# TDA2030.net
KiCad netlist of a schematic drawn in Altium Designer
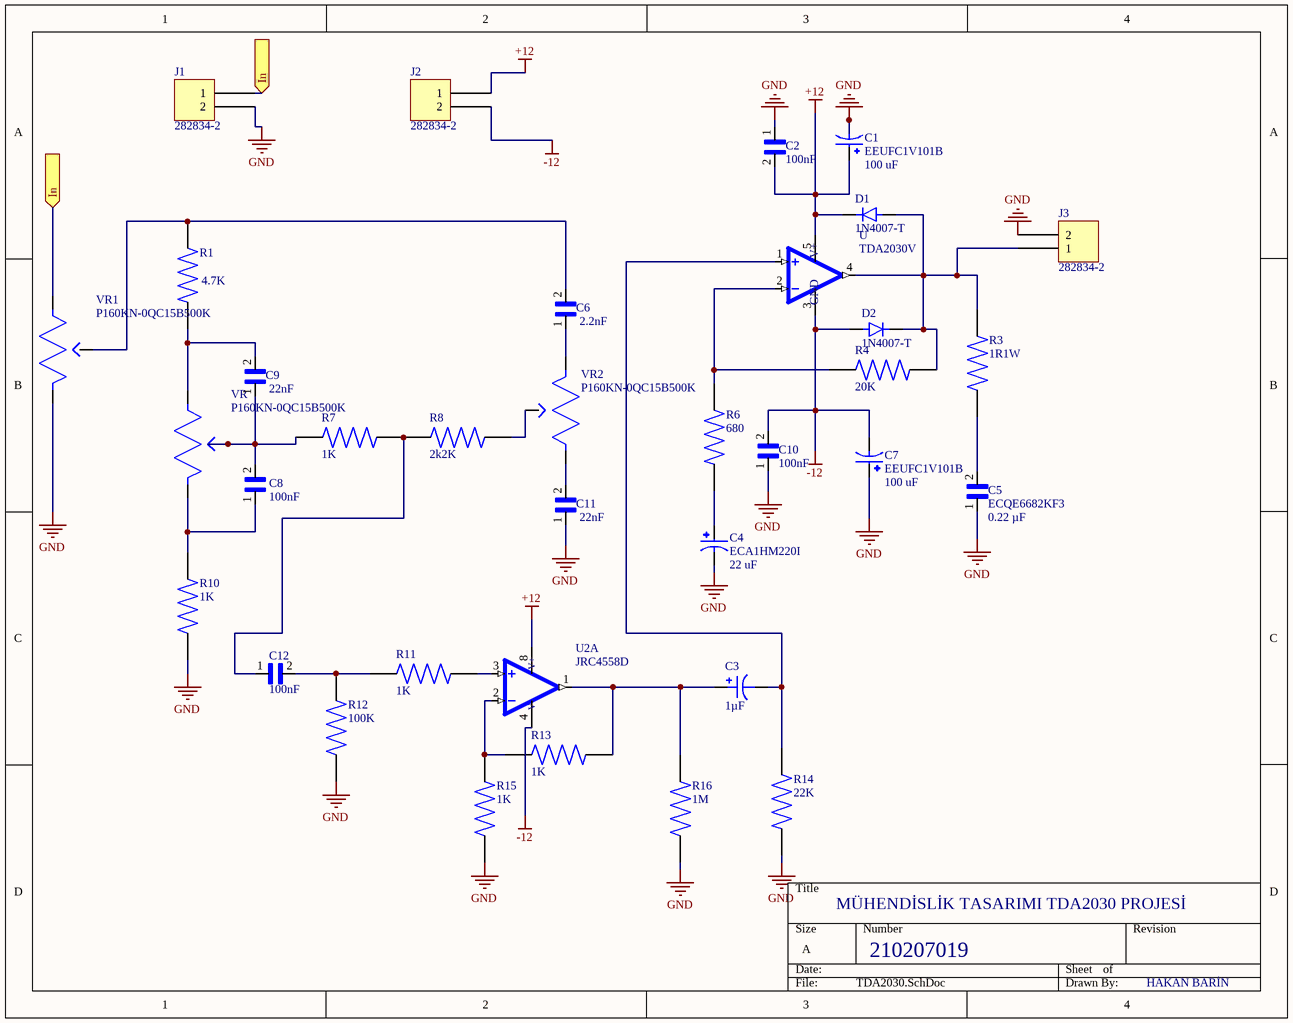
[diagram p0: TDA2030.SchDoc]

(export (version "E")
  (design (tool "Eeschema 10.0.6"))
  (components
    (comp (ref "C1")
      (value "EEUFC1V101B")
      (footprint "CAPPRD500W60D800H1150")
      (description "100F 35V Aluminum Electrolytic Capacitors Radial, Can 2000 Hrs @ 105C")
      (fields (field (name "MF") "Panasonic") (field (name "ALTIUM_VALUE") "100 uF"))
      (libsource (lib "EEUFC1V101B") (part "EEUFC1V101B"))
    )
    (comp (ref "C2")
      (value "100nF")
      (footprint "CAPRB500W50L450T300H550")
      (description "Cap Ceramic 1uF 50V X7R 10% Radial 5mm 125Â°C Tape")
      (fields (field (name "MF") "TDK") (field (name "MP") "FG24X7R1H105KRT06"))
      (libsource (lib "") (part "FG24X7R1H105KRT06_2"))
    )
    (comp (ref "C3")
      (value "1µF")
      (footprint "CAP TH ALUM ELEC D5.00mm S2.00mm H11.00mm")
      (description "CAP ALUM 1UF 20% 50V RADIAL")
      (fields (field (name "PART NUMBER") "RFS-50V010ME3#5") (field (name "MANUFACTURER") "Elna America"))
      (libsource (lib "Celestial Altium Library - altium_library") (part "Polarised Capacitor"))
    )
    (comp (ref "C4")
      (value "ECA1HM220I")
      (footprint "CAPPRD250W50D500H1100")
      (fields
        (field (name "ALTIUM_VALUE") "22 uF")
        (field (name "MF") "Panasonic")
        (field (name "MP") "ECA-1HM220I")
      )
      (libsource (lib "ECA1HM220I") (part "ECA1HM220I"))
    )
    (comp (ref "C5")
      (value "ECQE6682KF3")
      (footprint "CAPRR500W60L1200T490H1500")
      (fields (field (name "ALTIUM_VALUE") "0.22 µF"))
      (libsource (lib "ECQE6682KF3") (part "ECQE6682KF3"))
    )
    (comp (ref "C6")
      (value "2.2nF")
      (footprint "CAPRB500W50L450T300H550")
      (description "Cap Ceramic 1uF 50V X7R 10% Radial 5mm 125Â°C Tape")
      (fields (field (name "MF") "TDK") (field (name "MP") "FG24X7R1H105KRT06"))
      (libsource (lib "FG24X7R1H105KRT06") (part "FG24X7R1H105KRT06"))
    )
    (comp (ref "C7")
      (value "EEUFC1V101B")
      (footprint "CAPPRD500W60D800H1150")
      (description "100F 35V Aluminum Electrolytic Capacitors Radial, Can 2000 Hrs @ 105C")
      (fields (field (name "MF") "Panasonic") (field (name "ALTIUM_VALUE") "100 uF"))
      (libsource (lib "EEUFC1V101B") (part "EEUFC1V101B"))
    )
    (comp (ref "C8")
      (value "100nF")
      (footprint "CAPRB500W50L450T300H550")
      (description "Cap Ceramic 1uF 50V X7R 10% Radial 5mm 125Â°C Tape")
      (fields (field (name "MF") "TDK") (field (name "MP") "FG24X7R1H105KRT06"))
      (libsource (lib "FG24X7R1H105KRT06") (part "FG24X7R1H105KRT06"))
    )
    (comp (ref "C9")
      (value "22nF")
      (footprint "CAPRB500W50L450T300H550")
      (description "Cap Ceramic 1uF 50V X7R 10% Radial 5mm 125Â°C Tape")
      (fields (field (name "MF") "TDK") (field (name "MP") "FG24X7R1H105KRT06"))
      (libsource (lib "FG24X7R1H105KRT06") (part "FG24X7R1H105KRT06"))
    )
    (comp (ref "C10")
      (value "100nF")
      (footprint "CAPRB500W50L450T300H550")
      (description "Cap Ceramic 1uF 50V X7R 10% Radial 5mm 125Â°C Tape")
      (fields (field (name "MF") "TDK") (field (name "MP") "FG24X7R1H105KRT06"))
      (libsource (lib "FG24X7R1H105KRT06") (part "FG24X7R1H105KRT06"))
    )
    (comp (ref "C11")
      (value "22nF")
      (footprint "CAPRB500W50L450T300H550")
      (description "Cap Ceramic 1uF 50V X7R 10% Radial 5mm 125Â°C Tape")
      (fields (field (name "MF") "TDK") (field (name "MP") "FG24X7R1H105KRT06"))
      (libsource (lib "FG24X7R1H105KRT06") (part "FG24X7R1H105KRT06"))
    )
    (comp (ref "C12")
      (value "100nF")
      (footprint "CAPRB500W50L450T300H550")
      (description "Cap Ceramic 1uF 50V X7R 10% Radial 5mm 125Â°C Tape")
      (fields (field (name "MF") "TDK") (field (name "MP") "FG24X7R1H105KRT06"))
      (libsource (lib "") (part "FG24X7R1H105KRT06_1"))
    )
    (comp (ref "D1")
      (value "1N4007-T")
      (footprint "DIOAD780W78L463D236")
      (description "Diode Standard 1A 1000V 1Vf DO41 ¦ Diodes Inc 1N4007-T")
      (fields (field (name "MF") "Diodes Incorporated"))
      (libsource (lib "1N4007-T") (part "1N4007-T"))
    )
    (comp (ref "D2")
      (value "1N4007-T")
      (footprint "DIOAD780W78L463D236")
      (description "Diode Standard 1A 1000V 1Vf DO41 ¦ Diodes Inc 1N4007-T")
      (fields (field (name "MF") "Diodes Incorporated"))
      (libsource (lib "1N4007-T") (part "1N4007-T"))
    )
    (comp (ref "J1")
      (value "282834-2")
      (footprint "TE 282834-2")
      (description "TERM BLK 2P SIDE ENT 2.54MM PCB")
      (fields (field (name "MANUFACTURER") "TE Connectivity AMP Connectors") (field (name "VOLTAGE") "150V"))
      (libsource (lib "") (part "2 Pin_1"))
    )
    (comp (ref "J2")
      (value "282834-2")
      (footprint "TE 282834-2")
      (description "TERM BLK 2P SIDE ENT 2.54MM PCB")
      (fields (field (name "MANUFACTURER") "TE Connectivity AMP Connectors") (field (name "VOLTAGE") "150V"))
      (libsource (lib "") (part "2 Pin_1"))
    )
    (comp (ref "J3")
      (value "282834-2")
      (footprint "TE 282834-2")
      (description "TERM BLK 2P SIDE ENT 2.54MM PCB")
      (fields (field (name "MANUFACTURER") "TE Connectivity AMP Connectors") (field (name "VOLTAGE") "150V"))
      (libsource (lib "Celestial Altium Library - altium_library") (part "2 Pin"))
    )
    (comp (ref "R1")
      (value "4.7K")
      (footprint "RESAD1100W55L680D260")
      (description "1.07 kOhms Â±1% 0.25W, 1/4W Through Hole Resistor Axial - Metal Film")
      (fields (field (name "MF") "Yageo") (field (name "MP") "MFR-25FBF52-1K"))
      (libsource (lib "MFR-25FBF52-1K") (part "MFR-25FBF52-1K"))
    )
    (comp (ref "R3")
      (value "1R1W")
      (footprint "RESAD1100W55L680D260")
      (description "1.07 kOhms Â±1% 0.25W, 1/4W Through Hole Resistor Axial - Metal Film")
      (fields (field (name "MF") "Yageo") (field (name "MP") "MFR-25FBF52-1K"))
      (libsource (lib "MFR-25FBF52-1K") (part "MFR-25FBF52-1K"))
    )
    (comp (ref "R4")
      (value "20K")
      (footprint "RESAD1100W55L680D260")
      (description "1.07 kOhms Â±1% 0.25W, 1/4W Through Hole Resistor Axial - Metal Film")
      (fields (field (name "MF") "Yageo") (field (name "MP") "MFR-25FBF52-1K"))
      (libsource (lib "MFR-25FBF52-1K") (part "MFR-25FBF52-1K"))
    )
    (comp (ref "R6")
      (value "680")
      (footprint "RESAD1100W55L680D260")
      (description "1.07 kOhms Â±1% 0.25W, 1/4W Through Hole Resistor Axial - Metal Film")
      (fields (field (name "MF") "Yageo") (field (name "MP") "MFR-25FBF52-1K"))
      (libsource (lib "MFR-25FBF52-1K") (part "MFR-25FBF52-1K"))
    )
    (comp (ref "R7")
      (value "1K")
      (footprint "RESAD1100W55L680D260")
      (description "1.07 kOhms Â±1% 0.25W, 1/4W Through Hole Resistor Axial - Metal Film")
      (fields (field (name "MF") "Yageo") (field (name "MP") "MFR-25FBF52-1K"))
      (libsource (lib "MFR-25FBF52-1K") (part "MFR-25FBF52-1K"))
    )
    (comp (ref "R8")
      (value "2k2K")
      (footprint "RESAD1100W55L680D260")
      (description "1.07 kOhms Â±1% 0.25W, 1/4W Through Hole Resistor Axial - Metal Film")
      (fields (field (name "MF") "Yageo") (field (name "MP") "MFR-25FBF52-1K"))
      (libsource (lib "MFR-25FBF52-1K") (part "MFR-25FBF52-1K"))
    )
    (comp (ref "R10")
      (value "1K")
      (footprint "RESAD1100W55L680D260")
      (description "1.07 kOhms Â±1% 0.25W, 1/4W Through Hole Resistor Axial - Metal Film")
      (fields (field (name "MF") "Yageo") (field (name "MP") "MFR-25FBF52-1K"))
      (libsource (lib "MFR-25FBF52-1K") (part "MFR-25FBF52-1K"))
    )
    (comp (ref "R11")
      (value "1K")
      (footprint "RESAD1100W55L680D260")
      (description "1.07 kOhms Â±1% 0.25W, 1/4W Through Hole Resistor Axial - Metal Film")
      (fields (field (name "MF") "Yageo") (field (name "MP") "MFR-25FBF52-1K"))
      (libsource (lib "MFR-25FBF52-1K") (part "MFR-25FBF52-1K"))
    )
    (comp (ref "R12")
      (value "100K")
      (footprint "RESAD1100W55L680D260")
      (description "1.07 kOhms Â±1% 0.25W, 1/4W Through Hole Resistor Axial - Metal Film")
      (fields (field (name "MF") "Yageo") (field (name "MP") "MFR-25FBF52-1K"))
      (libsource (lib "MFR-25FBF52-1K") (part "MFR-25FBF52-1K"))
    )
    (comp (ref "R13")
      (value "1K")
      (footprint "RESAD1100W55L680D260")
      (description "1.07 kOhms Â±1% 0.25W, 1/4W Through Hole Resistor Axial - Metal Film")
      (fields (field (name "MF") "Yageo") (field (name "MP") "MFR-25FBF52-1K"))
      (libsource (lib "MFR-25FBF52-1K") (part "MFR-25FBF52-1K"))
    )
    (comp (ref "R14")
      (value "22K")
      (footprint "RESAD1100W55L680D260")
      (description "1.07 kOhms Â±1% 0.25W, 1/4W Through Hole Resistor Axial - Metal Film")
      (fields (field (name "MF") "Yageo") (field (name "MP") "MFR-25FBF52-1K"))
      (libsource (lib "MFR-25FBF52-1K") (part "MFR-25FBF52-1K"))
    )
    (comp (ref "R15")
      (value "1K")
      (footprint "RESAD1100W55L680D260")
      (description "1.07 kOhms Â±1% 0.25W, 1/4W Through Hole Resistor Axial - Metal Film")
      (fields (field (name "MF") "Yageo") (field (name "MP") "MFR-25FBF52-1K"))
      (libsource (lib "MFR-25FBF52-1K") (part "MFR-25FBF52-1K"))
    )
    (comp (ref "R16")
      (value "1M")
      (footprint "RESAD1100W55L680D260")
      (description "1.07 kOhms Â±1% 0.25W, 1/4W Through Hole Resistor Axial - Metal Film")
      (fields (field (name "MF") "Yageo") (field (name "MP") "MFR-25FBF52-1K"))
      (libsource (lib "MFR-25FBF52-1K") (part "MFR-25FBF52-1K"))
    )
    (comp (ref "U")
      (value "TDA2030V")
      (footprint "CB360")
      (description "Amplifier IC 1-Channel _Mono_ Class AB 5-PENTAWATT")
      (fields (field (name "MF") "STMicroelectronics"))
      (libsource (lib "TDA2030V") (part "TDA2030V"))
    )
    (comp (ref "U2")
      (value "JRC4558D")
      (footprint "DIP762W46P254L880H425Q8")
      (description "Dip8")
      (fields (field (name "MF") "New Japan Radio"))
      (libsource (lib "JRC4558D") (part "JRC4558D"))
    )
    (comp (ref "VR")
      (value "P160KN-0QC15B500K")
      (footprint "P160")
      (description "500k Ohm 1 Gang Linear Panel Mount Potentiometer None 1 Turn Conductive Plastic 0.2W, 1/5W PC Pins")
      (fields (field (name "MF") "TT Electronics/BI") (field (name "DIGI-KEY_PART_NUMBER") "987-1304-ND"))
      (libsource (lib "P160KN-0QC15B500K") (part "P160KN-0QC15B500K"))
    )
    (comp (ref "VR1")
      (value "P160KN-0QC15B500K")
      (footprint "P160")
      (description "500k Ohm 1 Gang Linear Panel Mount Potentiometer None 1 Turn Conductive Plastic 0.2W, 1/5W PC Pins")
      (fields (field (name "MF") "TT Electronics/BI") (field (name "DIGI-KEY_PART_NUMBER") "987-1304-ND"))
      (libsource (lib "P160KN-0QC15B500K") (part "P160KN-0QC15B500K"))
    )
    (comp (ref "VR2")
      (value "P160KN-0QC15B500K")
      (footprint "P160")
      (description "500k Ohm 1 Gang Linear Panel Mount Potentiometer None 1 Turn Conductive Plastic 0.2W, 1/5W PC Pins")
      (fields (field (name "MF") "TT Electronics/BI") (field (name "DIGI-KEY_PART_NUMBER") "987-1304-ND"))
      (libsource (lib "P160KN-0QC15B500K") (part "P160KN-0QC15B500K"))
    )
  )
  (nets
    (net (code "1") (name "+12") (class "Default")
      (node (ref "C1") (pin "P") (pinfunction "P_P") (pintype "passive"))
      (node (ref "C2") (pin "2") (pinfunction "2_2") (pintype "passive"))
      (node (ref "D1") (pin "K") (pinfunction "K_K") (pintype "passive"))
      (node (ref "J2") (pin "1") (pinfunction "1_1") (pintype "passive"))
      (node (ref "U") (pin "5") (pinfunction "V+_5") (pintype "power_in"))
      (node (ref "U2") (pin "8") (pinfunction "V+_8") (pintype "power_in"))
    )
    (net (code "2") (name "-12") (class "Default")
      (node (ref "C10") (pin "2") (pinfunction "2_2") (pintype "passive"))
      (node (ref "C7") (pin "N") (pinfunction "N_N") (pintype "passive"))
      (node (ref "D2") (pin "A") (pinfunction "A_A") (pintype "passive"))
      (node (ref "J2") (pin "2") (pinfunction "2_2") (pintype "passive"))
      (node (ref "U") (pin "3") (pinfunction "GND_3") (pintype "power_in"))
      (node (ref "U2") (pin "4") (pinfunction "V-_4") (pintype "power_in"))
    )
    (net (code "3") (name "/In") (class "Default")
      (node (ref "J1") (pin "1") (pinfunction "1_1") (pintype "passive"))
      (node (ref "VR1") (pin "3") (pinfunction "3_3") (pintype "bidirectional"))
    )
    (net (code "4") (name "GND") (class "Default")
      (node (ref "C1") (pin "N") (pinfunction "N_N") (pintype "passive"))
      (node (ref "C10") (pin "1") (pinfunction "1_1") (pintype "passive"))
      (node (ref "C11") (pin "1") (pinfunction "1_1") (pintype "passive"))
      (node (ref "C2") (pin "1") (pinfunction "1_1") (pintype "passive"))
      (node (ref "C4") (pin "N") (pinfunction "N_N") (pintype "passive"))
      (node (ref "C5") (pin "1") (pinfunction "1_1") (pintype "passive"))
      (node (ref "C7") (pin "P") (pinfunction "P_P") (pintype "passive"))
      (node (ref "J1") (pin "2") (pinfunction "2_2") (pintype "passive"))
      (node (ref "J3") (pin "2") (pinfunction "2_2") (pintype "passive"))
      (node (ref "R10") (pin "2") (pinfunction "2_2") (pintype "passive"))
      (node (ref "R12") (pin "2") (pinfunction "2_2") (pintype "passive"))
      (node (ref "R14") (pin "2") (pinfunction "2_2") (pintype "passive"))
      (node (ref "R15") (pin "2") (pinfunction "2_2") (pintype "passive"))
      (node (ref "R16") (pin "2") (pinfunction "2_2") (pintype "passive"))
      (node (ref "VR1") (pin "1") (pinfunction "1_1") (pintype "bidirectional"))
    )
    (net (code "5") (name "Net-(C4-PadP)") (class "Default")
      (node (ref "C4") (pin "P") (pinfunction "P_P") (pintype "passive"))
      (node (ref "R6") (pin "2") (pinfunction "2_2") (pintype "passive"))
    )
    (net (code "6") (name "Net-(C5-Pad2)") (class "Default")
      (node (ref "C5") (pin "2") (pinfunction "2_2") (pintype "passive"))
      (node (ref "R3") (pin "2") (pinfunction "2_2") (pintype "passive"))
    )
    (net (code "7") (name "Net-(C6-Pad1)") (class "Default")
      (node (ref "C6") (pin "1") (pinfunction "1_1") (pintype "passive"))
      (node (ref "VR2") (pin "1") (pinfunction "1_1") (pintype "bidirectional"))
    )
    (net (code "8") (name "Net-(C6-Pad2)") (class "Default")
      (node (ref "C6") (pin "2") (pinfunction "2_2") (pintype "passive"))
      (node (ref "R1") (pin "2") (pinfunction "2_2") (pintype "passive"))
      (node (ref "VR1") (pin "2") (pinfunction "2_2") (pintype "bidirectional"))
    )
    (net (code "9") (name "Net-(C8-Pad1)") (class "Default")
      (node (ref "C8") (pin "1") (pinfunction "1_1") (pintype "passive"))
      (node (ref "R10") (pin "1") (pinfunction "1_1") (pintype "passive"))
      (node (ref "VR") (pin "1") (pinfunction "1_1") (pintype "bidirectional"))
    )
    (net (code "10") (name "Net-(C8-Pad2)") (class "Default")
      (node (ref "C8") (pin "2") (pinfunction "2_2") (pintype "passive"))
      (node (ref "C9") (pin "1") (pinfunction "1_1") (pintype "passive"))
      (node (ref "R7") (pin "2") (pinfunction "2_2") (pintype "passive"))
      (node (ref "VR") (pin "2") (pinfunction "2_2") (pintype "bidirectional"))
    )
    (net (code "11") (name "Net-(C9-Pad2)") (class "Default")
      (node (ref "C9") (pin "2") (pinfunction "2_2") (pintype "passive"))
      (node (ref "R1") (pin "1") (pinfunction "1_1") (pintype "passive"))
      (node (ref "VR") (pin "3") (pinfunction "3_3") (pintype "bidirectional"))
    )
    (net (code "12") (name "Net-(C11-Pad2)") (class "Default")
      (node (ref "C11") (pin "2") (pinfunction "2_2") (pintype "passive"))
      (node (ref "VR2") (pin "3") (pinfunction "3_3") (pintype "bidirectional"))
    )
    (net (code "13") (name "Net-(C12-Pad1)") (class "Default")
      (node (ref "C12") (pin "1") (pinfunction "1_1") (pintype "passive"))
      (node (ref "R7") (pin "1") (pinfunction "1_1") (pintype "passive"))
      (node (ref "R8") (pin "2") (pinfunction "2_2") (pintype "passive"))
    )
    (net (code "14") (name "Net-(C12-Pad2)") (class "Default")
      (node (ref "C12") (pin "2") (pinfunction "2_2") (pintype "passive"))
      (node (ref "R11") (pin "1") (pinfunction "1_1") (pintype "passive"))
      (node (ref "R12") (pin "1") (pinfunction "1_1") (pintype "passive"))
    )
    (net (code "15") (name "Net-(R8-Pad1)") (class "Default")
      (node (ref "R8") (pin "1") (pinfunction "1_1") (pintype "passive"))
      (node (ref "VR2") (pin "2") (pinfunction "2_2") (pintype "bidirectional"))
    )
    (net (code "16") (name "Net-(U-+IN)") (class "Default")
      (node (ref "C3") (pin "2") (pinfunction "2_2") (pintype "passive"))
      (node (ref "R14") (pin "1") (pinfunction "1_1") (pintype "passive"))
      (node (ref "U") (pin "1") (pinfunction "+IN_1") (pintype "input"))
    )
    (net (code "17") (name "Net-(U--IN)") (class "Default")
      (node (ref "R4") (pin "1") (pinfunction "1_1") (pintype "passive"))
      (node (ref "R6") (pin "1") (pinfunction "1_1") (pintype "passive"))
      (node (ref "U") (pin "2") (pinfunction "-IN_2") (pintype "input"))
    )
    (net (code "18") (name "Net-(U-OUT)") (class "Default")
      (node (ref "D1") (pin "A") (pinfunction "A_A") (pintype "passive"))
      (node (ref "D2") (pin "K") (pinfunction "K_K") (pintype "passive"))
      (node (ref "J3") (pin "1") (pinfunction "1_1") (pintype "passive"))
      (node (ref "R3") (pin "1") (pinfunction "1_1") (pintype "passive"))
      (node (ref "R4") (pin "2") (pinfunction "2_2") (pintype "passive"))
      (node (ref "U") (pin "4") (pinfunction "OUT_4") (pintype "output"))
    )
    (net (code "19") (name "Net-(U2A-+IN)") (class "Default")
      (node (ref "R11") (pin "2") (pinfunction "2_2") (pintype "passive"))
      (node (ref "U2") (pin "3") (pinfunction "+IN_3") (pintype "input"))
    )
    (net (code "20") (name "Net-(U2A--IN)") (class "Default")
      (node (ref "R13") (pin "1") (pinfunction "1_1") (pintype "passive"))
      (node (ref "R15") (pin "1") (pinfunction "1_1") (pintype "passive"))
      (node (ref "U2") (pin "2") (pinfunction "-IN_2") (pintype "input"))
    )
    (net (code "21") (name "Net-(U2A-OUT)") (class "Default")
      (node (ref "C3") (pin "1") (pinfunction "1_1") (pintype "passive"))
      (node (ref "R13") (pin "2") (pinfunction "2_2") (pintype "passive"))
      (node (ref "R16") (pin "1") (pinfunction "1_1") (pintype "passive"))
      (node (ref "U2") (pin "1") (pinfunction "OUT_1") (pintype "output"))
    )
  )
)
